# Sensor_GP1A57HRJ00F_board_V_1_0.net
KiCad netlist of a schematic drawn in EAGLE
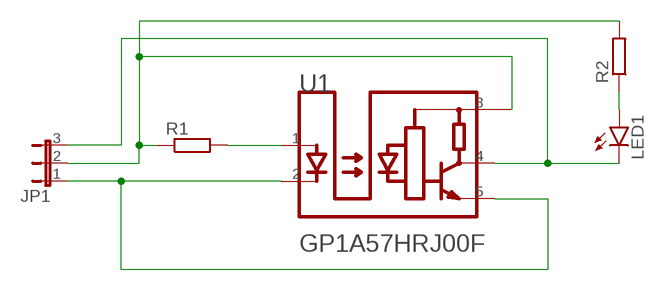
[diagram p0: schematic, sheet 1]

(export (version "E")
  (design (tool "Eeschema 10.0.6"))
  (components
    (comp (ref "JP1")
      (value "JP2E")
      (footprint "eagle-import:JP2")
      (libsource (lib "eagle-import") (part "JP2E"))
    )
    (comp (ref "LED1")
      (value "LED3MM")
      (footprint "eagle-import:LED3MM")
      (libsource (lib "eagle-import") (part "LED3MM"))
    )
    (comp (ref "R1")
      (value "R-EU_0309/10")
      (footprint "eagle-import:0309_10")
      (libsource (lib "eagle-import") (part "R-EU_0309/10"))
    )
    (comp (ref "R2")
      (value "R-EU_0309/10")
      (footprint "eagle-import:0309_10")
      (libsource (lib "eagle-import") (part "R-EU_0309/10"))
    )
    (comp (ref "U1")
      (value "SHARP_GP1A57HRJ00FSHARP_GP1A57HRJ00F_0_0")
      (footprint "eagle-import:SHARP_GP1A57HRJ00F_0")
      (fields
        (field (name "DIGIKEY_PART_NUMBER") "1855-1043-ND")
        (field (name "MF") "Sharp")
        (field (name "MOUSER_PART_NUMBER") "852-GP1A57HRJ00F")
      )
      (libsource (lib "eagle-import") (part "SHARP_GP1A57HRJ00FSHARP_GP1A57HRJ00F_0_0"))
    )
  )
  (nets
    (net (code "1") (name "Net-(LED1-C)") (class "Default")
      (node (ref "JP1") (pin "3") (pinfunction "3_3") (pintype "passive"))
      (node (ref "LED1") (pin "K") (pinfunction "C_K") (pintype "passive"))
      (node (ref "U1") (pin "4") (pinfunction "VO_4") (pintype "output"))
    )
    (net (code "2") (name "Net-(LED1-PadA)") (class "Default")
      (node (ref "LED1") (pin "A") (pinfunction "A_A") (pintype "passive"))
      (node (ref "R2") (pin "1") (pinfunction "1_1") (pintype "passive"))
    )
    (net (code "3") (name "Net-(U1-ANODE)") (class "Default")
      (node (ref "R1") (pin "2") (pinfunction "2_2") (pintype "passive"))
      (node (ref "U1") (pin "1") (pinfunction "ANODE_1") (pintype "passive"))
    )
    (net (code "4") (name "Net-(U1-CATHODE)") (class "Default")
      (node (ref "JP1") (pin "1") (pinfunction "1_1") (pintype "passive"))
      (node (ref "U1") (pin "2") (pinfunction "CATHODE_2") (pintype "passive"))
      (node (ref "U1") (pin "5") (pinfunction "GND_5") (pintype "power_in"))
    )
    (net (code "5") (name "Net-(U1-VCC)") (class "Default")
      (node (ref "JP1") (pin "2") (pinfunction "2_2") (pintype "passive"))
      (node (ref "R1") (pin "1") (pinfunction "1_1") (pintype "passive"))
      (node (ref "R2") (pin "2") (pinfunction "2_2") (pintype "passive"))
      (node (ref "U1") (pin "3") (pinfunction "VCC_3") (pintype "power_in"))
    )
  )
)
